# Sheet1.net
KiCad netlist of a schematic drawn in Altium Designer
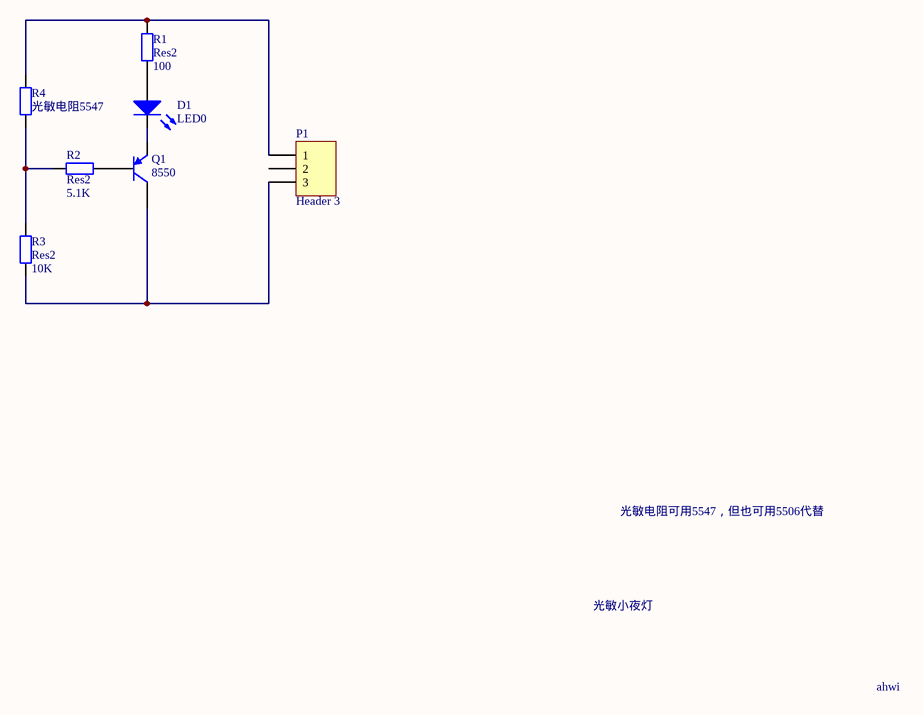
[diagram p0: Sheet1.SchDoc]

(export (version "E")
  (design (tool "Eeschema 10.0.6"))
  (components
    (comp (ref "D1")
      (value "LED0")
      (footprint "6-0805_M")
      (description "Typical INFRARED GaAs LED")
      (fields (field (name "PUBLISHER") "Altium Limited"))
      (libsource (lib "Miscellaneous Devices") (part "LED0"))
    )
    (comp (ref "P1")
      (value "Header 3")
      (footprint "PCBComponent_1")
      (description "Header, 3-Pin")
      (fields (field (name "PUBLISHER") "Altium Limited"))
      (libsource (lib "Miscellaneous Connectors") (part "Header 3"))
    )
    (comp (ref "Q1")
      (value "8550")
      (footprint "SOT-23B_L")
      (description "PNP Bipolar Transistor")
      (fields (field (name "PUBLISHER") "Altium Limited"))
      (libsource (lib "Miscellaneous Devices") (part "PNP"))
    )
    (comp (ref "R1")
      (value "Res2")
      (footprint "6-0805_M")
      (description "Resistor")
      (fields (field (name "ALTIUM_VALUE") "100") (field (name "PUBLISHER") "Altium Limited"))
      (libsource (lib "Miscellaneous Devices") (part "Res2"))
    )
    (comp (ref "R2")
      (value "Res2")
      (footprint "6-0805_M")
      (description "Resistor")
      (fields (field (name "ALTIUM_VALUE") "5.1K") (field (name "PUBLISHER") "Altium Limited"))
      (libsource (lib "") (part "Res2_1"))
    )
    (comp (ref "R3")
      (value "Res2")
      (footprint "6-0805_M")
      (description "Resistor")
      (fields (field (name "ALTIUM_VALUE") "10K") (field (name "PUBLISHER") "Altium Limited"))
      (libsource (lib "Miscellaneous Devices") (part "Res2"))
    )
    (comp (ref "R4")
      (value "光敏电阻5547")
      (footprint "R38")
      (description "Resistor")
      (fields (field (name "PUBLISHER") "Altium Limited"))
      (libsource (lib "Miscellaneous Devices") (part "Res2"))
    )
  )
  (nets
    (net (code "1") (name "Net-(D1-A)") (class "Default")
      (node (ref "D1") (pin "1") (pinfunction "A_1") (pintype "passive"))
      (node (ref "R1") (pin "1") (pinfunction "1_1") (pintype "passive"))
    )
    (net (code "2") (name "Net-(D1-K)") (class "Default")
      (node (ref "D1") (pin "2") (pinfunction "K_2") (pintype "passive"))
      (node (ref "Q1") (pin "3") (pinfunction "E_3") (pintype "passive"))
    )
    (net (code "3") (name "Net-(P1-Pad1)") (class "Default")
      (node (ref "P1") (pin "1") (pinfunction "1_1") (pintype "passive"))
      (node (ref "R1") (pin "2") (pinfunction "2_2") (pintype "passive"))
      (node (ref "R4") (pin "2") (pinfunction "2_2") (pintype "passive"))
    )
    (net (code "4") (name "Net-(Q1-B)") (class "Default")
      (node (ref "Q1") (pin "2") (pinfunction "B_2") (pintype "passive"))
      (node (ref "R2") (pin "2") (pinfunction "2_2") (pintype "passive"))
    )
    (net (code "5") (name "Net-(Q1-C)") (class "Default")
      (node (ref "P1") (pin "3") (pinfunction "3_3") (pintype "passive"))
      (node (ref "Q1") (pin "1") (pinfunction "C_1") (pintype "passive"))
      (node (ref "R3") (pin "1") (pinfunction "1_1") (pintype "passive"))
    )
    (net (code "6") (name "Net-(R2-Pad1)") (class "Default")
      (node (ref "R2") (pin "1") (pinfunction "1_1") (pintype "passive"))
      (node (ref "R3") (pin "2") (pinfunction "2_2") (pintype "passive"))
      (node (ref "R4") (pin "1") (pinfunction "1_1") (pintype "passive"))
    )
    (net (code "7") (name "unconnected-(P1-Pad2)") (class "Default")
      (node (ref "P1") (pin "2") (pinfunction "2_2") (pintype "passive"))
    )
  )
)
